# SCH_LinBridge_3_0_2026-08-19_sanitized.net
KiCad netlist of a schematic drawn in EasyEDA
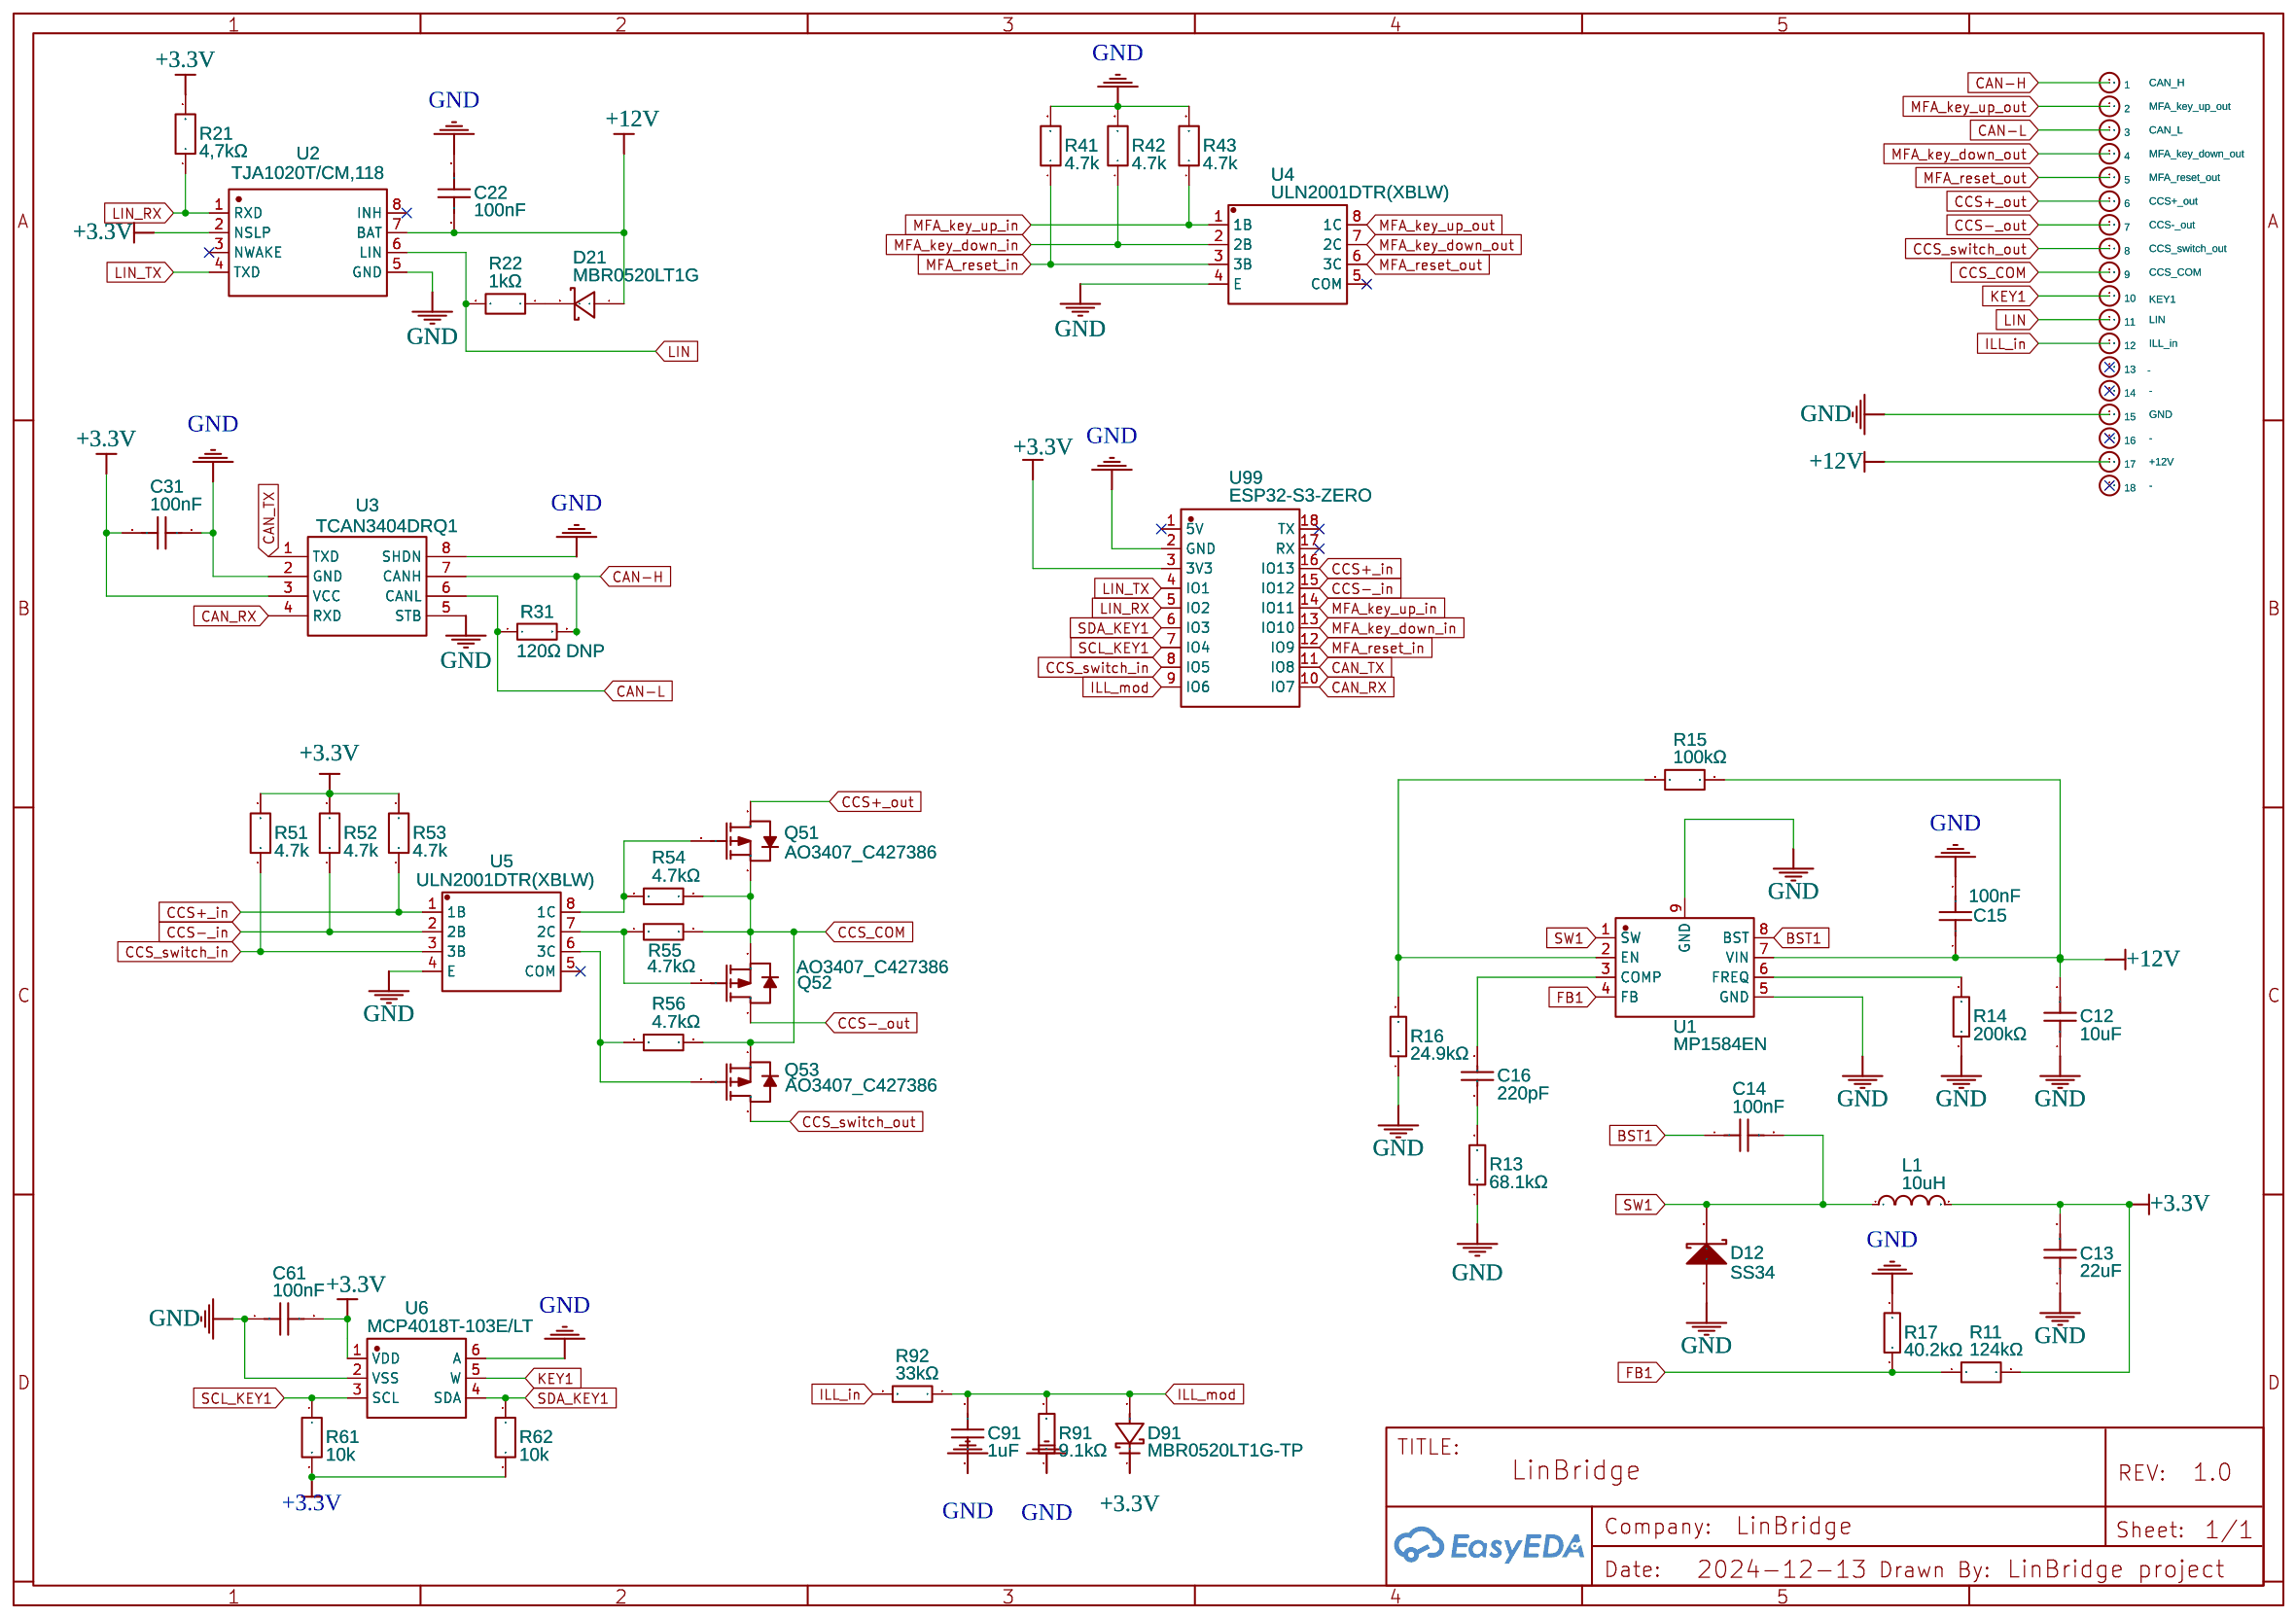
[diagram p0: schematic sheet]

(export (version "E")
  (design (tool "Eeschema 10.0.6"))
  (components
    (comp (ref "1") (value "CAN_H") (libsource (lib "") (part "Through_Hole_1mm")))
    (comp (ref "2") (value "MFA_key_up_out") (libsource (lib "") (part "Through_Hole_1mm")))
    (comp (ref "3") (value "CAN_L") (libsource (lib "") (part "Through_Hole_1mm")))
    (comp (ref "4") (value "MFA_key_down_out") (libsource (lib "") (part "Through_Hole_1mm")))
    (comp (ref "5") (value "MFA_reset_out") (libsource (lib "") (part "Through_Hole_1mm")))
    (comp (ref "6") (value "CCS+_out") (libsource (lib "") (part "Through_Hole_1mm")))
    (comp (ref "7") (value "CCS-_out") (libsource (lib "") (part "Through_Hole_1mm")))
    (comp (ref "8") (value "CCS_switch_out") (libsource (lib "") (part "Through_Hole_1mm")))
    (comp (ref "9") (value "CCS_COM") (libsource (lib "") (part "Through_Hole_1mm")))
    (comp (ref "10") (value "KEY1") (libsource (lib "") (part "Through_Hole_1mm")))
    (comp (ref "11") (value "LIN") (libsource (lib "") (part "Through_Hole_1mm")))
    (comp (ref "12") (value "ILL_in") (libsource (lib "") (part "Through_Hole_1mm")))
    (comp (ref "13") (value "-") (libsource (lib "") (part "Through_Hole_1mm")))
    (comp (ref "14") (value "-") (libsource (lib "") (part "Through_Hole_1mm")))
    (comp (ref "15") (value "GND") (libsource (lib "") (part "Through_Hole_1mm")))
    (comp (ref "16") (value "-") (libsource (lib "") (part "Through_Hole_1mm")))
    (comp (ref "17") (value "+12V") (libsource (lib "") (part "Through_Hole_1mm")))
    (comp (ref "18") (value "-") (libsource (lib "") (part "Through_Hole_1mm")))
    (comp (ref "C12") (value "10uF") (libsource (lib "") (part "TCC1206X5R106K500HT")))
    (comp (ref "C13") (value "22uF") (libsource (lib "") (part "TCC1206X7R226M100HT")))
    (comp (ref "C14") (value "100nF") (libsource (lib "") (part "TCC0603X7R104K250CT")))
    (comp (ref "C15")
      (value "100nF")
      (fields
        (field (name "Manufacturer Part") "C0805C104K5RAC7411")
        (field (name "Manufacturer") "KEMET(基美)")
      )
      (libsource (lib "") (part "C0805C104K5RAC7411"))
    )
    (comp (ref "C16") (value "220pF") (libsource (lib "") (part "CC0603JRNPO9BN221")))
    (comp (ref "C22")
      (value "100nF")
      (fields
        (field (name "Manufacturer Part") "C0805C104K5RAC7411")
        (field (name "Manufacturer") "KEMET(基美)")
      )
      (libsource (lib "") (part "C0805C104K5RAC7411"))
    )
    (comp (ref "C31")
      (value "100nF")
      (fields (field (name "Manufacturer Part") "C0805X104K050T") (field (name "Manufacturer") "IHHEC(禾伸堂)"))
      (libsource (lib "") (part "C0805-100NF"))
    )
    (comp (ref "C61")
      (value "100nF")
      (fields
        (field (name "Manufacturer Part") "CC0805KRX7R7BB104")
        (field (name "Manufacturer") "YAGEO(国巨)")
      )
      (libsource (lib "") (part "CC0805KRX7R7BB104"))
    )
    (comp (ref "C91")
      (value "1uF")
      (fields (field (name "Manufacturer Part") "C0805C105K5RACTU") (field (name "Manufacturer") "KEMET(基美)"))
      (libsource (lib "") (part "C0805C105K5RACTU"))
    )
    (comp (ref "D12")
      (value "SS34")
      (fields (field (name "Manufacturer") "ON"))
      (libsource (lib "") (part "Unknown_842_-178"))
    )
    (comp (ref "D21") (value "MBR0520LT1G") (libsource (lib "") (part "MBR0520LT1G")))
    (comp (ref "D91")
      (value "MBR0520LT1G-TP")
      (fields (field (name "Manufacturer") "TECH PUBLIC(台舟)"))
      (libsource (lib "") (part "MBR0520LT1G-TP"))
    )
    (comp (ref "L1")
      (value "10uH")
      (fields (field (name "Manufacturer Part") "SMNR4020-10UH") (field (name "Manufacturer") "SXN(顺翔诺)"))
      (libsource (lib "") (part "SMNR4020-10UH"))
    )
    (comp (ref "Q51")
      (value "AO3407_C427386")
      (fields (field (name "Manufacturer Part") "MDD3407") (field (name "Manufacturer") "MDD(辰达半导体)"))
      (libsource (lib "") (part "AO3407_C427386_1"))
    )
    (comp (ref "Q52")
      (value "AO3407_C427386")
      (fields (field (name "Manufacturer Part") "MDD3407") (field (name "Manufacturer") "MDD(辰达半导体)"))
      (libsource (lib "") (part "AO3407_C427386"))
    )
    (comp (ref "Q53")
      (value "AO3407_C427386")
      (fields (field (name "Manufacturer Part") "MDD3407") (field (name "Manufacturer") "MDD(辰达半导体)"))
      (libsource (lib "") (part "AO3407_C427386"))
    )
    (comp (ref "R11") (value "124kΩ") (libsource (lib "") (part "TD03G1243BT")))
    (comp (ref "R13") (value "68.1kΩ") (libsource (lib "") (part "0402WGF6812TCE")))
    (comp (ref "R14") (value "200kΩ") (libsource (lib "") (part "CR1206F42003G")))
    (comp (ref "R15") (value "100kΩ") (libsource (lib "") (part "1210W2F1003T5E")))
    (comp (ref "R16") (value "24.9kΩ") (libsource (lib "") (part "0402WGF2492TCE")))
    (comp (ref "R17") (value "40.2kΩ") (libsource (lib "") (part "RTT034022FTP")))
    (comp (ref "R21")
      (value "4,7kΩ")
      (fields (field (name "Manufacturer Part") "APC0805B1K00N") (field (name "Manufacturer") "Ohmite"))
      (libsource (lib "") (part "APC0805B1K00N"))
    )
    (comp (ref "R22")
      (value "1kΩ")
      (fields (field (name "Manufacturer Part") "APC0805B1K00N") (field (name "Manufacturer") "Ohmite"))
      (libsource (lib "") (part "APC0805B1K00N_1"))
    )
    (comp (ref "R31")
      (value "120Ω DNP")
      (fields (field (name "Manufacturer Part") "TC052B1200T5E") (field (name "Manufacturer") "UniOhm"))
      (libsource (lib "") (part "120Ω 0,1%"))
    )
    (comp (ref "R41")
      (value "4.7k")
      (fields (field (name "Manufacturer Part") "RC0805FR-074K7L") (field (name "Manufacturer") "YAGEO(国巨)"))
      (libsource (lib "") (part "R_0603_EU"))
    )
    (comp (ref "R42")
      (value "4.7k")
      (fields (field (name "Manufacturer Part") "RC0805FR-074K7L") (field (name "Manufacturer") "YAGEO(国巨)"))
      (libsource (lib "") (part "R_0603_EU"))
    )
    (comp (ref "R43")
      (value "4.7k")
      (fields (field (name "Manufacturer Part") "RC0805FR-074K7L") (field (name "Manufacturer") "YAGEO(国巨)"))
      (libsource (lib "") (part "R_0603_EU"))
    )
    (comp (ref "R51")
      (value "4.7k")
      (fields (field (name "Manufacturer Part") "RC0805FR-074K7L") (field (name "Manufacturer") "YAGEO(国巨)"))
      (libsource (lib "") (part "R_0603_EU"))
    )
    (comp (ref "R52")
      (value "4.7k")
      (fields (field (name "Manufacturer Part") "RC0805FR-074K7L") (field (name "Manufacturer") "YAGEO(国巨)"))
      (libsource (lib "") (part "R_0603_EU"))
    )
    (comp (ref "R53")
      (value "4.7k")
      (fields (field (name "Manufacturer Part") "RC0805FR-074K7L") (field (name "Manufacturer") "YAGEO(国巨)"))
      (libsource (lib "") (part "R_0603_EU"))
    )
    (comp (ref "R54")
      (value "4.7kΩ")
      (fields (field (name "Manufacturer Part") "RMC08054.7K1%N") (field (name "Manufacturer") "Tyohm(幸亚电阻)"))
      (libsource (lib "") (part "RMC08054.7K1%N"))
    )
    (comp (ref "R55")
      (value "4.7kΩ")
      (fields (field (name "Manufacturer Part") "RMC08054.7K1%N") (field (name "Manufacturer") "Tyohm(幸亚电阻)"))
      (libsource (lib "") (part "RMC08054.7K1%N"))
    )
    (comp (ref "R56")
      (value "4.7kΩ")
      (fields (field (name "Manufacturer Part") "RMC08054.7K1%N") (field (name "Manufacturer") "Tyohm(幸亚电阻)"))
      (libsource (lib "") (part "RMC08054.7K1%N"))
    )
    (comp (ref "R61")
      (value "10k")
      (fields (field (name "Manufacturer Part") "SCR0805F10K") (field (name "Manufacturer") "VO(翔胜)"))
      (libsource (lib "") (part "R_0603_EU_1"))
    )
    (comp (ref "R62")
      (value "10k")
      (fields (field (name "Manufacturer Part") "SCR0805F10K") (field (name "Manufacturer") "VO(翔胜)"))
      (libsource (lib "") (part "R_0603_EU_1"))
    )
    (comp (ref "R91")
      (value "9.1kΩ")
      (fields (field (name "Manufacturer Part") "RMC08059.1K1%N") (field (name "Manufacturer") "Tyohm(幸亚电阻)"))
      (libsource (lib "") (part "RMC08059.1K1%N"))
    )
    (comp (ref "R92")
      (value "33kΩ")
      (fields (field (name "Manufacturer Part") "AECR0805F27K0K9") (field (name "Manufacturer") "RESI(开步睿思)"))
      (libsource (lib "") (part "AECR0805F27K0K9"))
    )
    (comp (ref "U1") (value "MP1584EN") (libsource (lib "") (part "MP1584EN")))
    (comp (ref "U2")
      (value "TJA1020T/CM,118")
      (fields (field (name "Manufacturer") "NXP(恩智浦)"))
      (libsource (lib "") (part "TJA1020T/CM,118"))
    )
    (comp (ref "U3")
      (value "TCAN3404DRQ1")
      (fields (field (name "Manufacturer Part") "TJA1050T/CM,118") (field (name "Manufacturer") "NXP"))
      (libsource (lib "") (part "TJA1050T/CM,118"))
    )
    (comp (ref "U4")
      (value "ULN2001DTR(XBLW)")
      (fields (field (name "Manufacturer") "XBLW(芯伯乐)"))
      (libsource (lib "") (part "ULN2001DTR(XBLW)"))
    )
    (comp (ref "U5")
      (value "ULN2001DTR(XBLW)")
      (fields (field (name "Manufacturer") "XBLW(芯伯乐)"))
      (libsource (lib "") (part "ULN2001DTR(XBLW)"))
    )
    (comp (ref "U6")
      (value "MCP4018T-103E/LT")
      (fields
        (field (name "Manufacturer Part") "MCP4018T-104E/LT")
        (field (name "Manufacturer") "MICROCHIP(美国微芯)")
      )
      (libsource (lib "") (part "MCP4018T-104E/LT"))
    )
    (comp (ref "U99")
      (value "ESP32-S3-ZERO")
      (fields (field (name "Manufacturer Part") "ESP32-S3-Zero"))
      (libsource (lib "") (part "ESP32-S3-ZERO"))
    )
  )
  (nets
    (net (code "1") (name "+3.3V") (class "Default")
      (node (ref "C13") (pin "2") (pinfunction "2_2") (pintype "unspecified"))
      (node (ref "C31") (pin "2") (pinfunction "2_2") (pintype "unspecified"))
      (node (ref "C61") (pin "2") (pinfunction "2_2") (pintype "unspecified"))
      (node (ref "D91") (pin "1") (pinfunction "K_1") (pintype "unspecified"))
      (node (ref "L1") (pin "2") (pinfunction "2_2") (pintype "unspecified"))
      (node (ref "R11") (pin "2") (pinfunction "2_2") (pintype "unspecified"))
      (node (ref "R21") (pin "2") (pinfunction "2_2") (pintype "unspecified"))
      (node (ref "R51") (pin "2") (pinfunction "2_2") (pintype "unspecified"))
      (node (ref "R52") (pin "2") (pinfunction "2_2") (pintype "unspecified"))
      (node (ref "R53") (pin "2") (pinfunction "2_2") (pintype "unspecified"))
      (node (ref "R61") (pin "2") (pinfunction "2_2") (pintype "unspecified"))
      (node (ref "R62") (pin "2") (pinfunction "2_2") (pintype "unspecified"))
      (node (ref "U2") (pin "2") (pinfunction "NSLP_2") (pintype "unspecified"))
      (node (ref "U3") (pin "3") (pinfunction "VCC_3") (pintype "unspecified"))
      (node (ref "U6") (pin "1") (pinfunction "VDD_1") (pintype "unspecified"))
      (node (ref "U99") (pin "3") (pinfunction "3V3_3") (pintype "unspecified"))
    )
    (net (code "2") (name "+12V") (class "Default")
      (node (ref "17") (pin "1") (pinfunction "1_1") (pintype "unspecified"))
      (node (ref "C12") (pin "2") (pinfunction "2_2") (pintype "unspecified"))
      (node (ref "C15") (pin "1") (pinfunction "1_1") (pintype "unspecified"))
      (node (ref "C22") (pin "1") (pinfunction "1_1") (pintype "unspecified"))
      (node (ref "D21") (pin "1") (pinfunction "A_1") (pintype "unspecified"))
      (node (ref "R15") (pin "2") (pinfunction "2_2") (pintype "unspecified"))
      (node (ref "U1") (pin "7") (pinfunction "VIN_7") (pintype "unspecified"))
      (node (ref "U2") (pin "7") (pinfunction "BAT_7") (pintype "unspecified"))
    )
    (net (code "3") (name "BST1") (class "Default")
      (node (ref "C14") (pin "1") (pinfunction "1_1") (pintype "unspecified"))
      (node (ref "U1") (pin "8") (pinfunction "BST_8") (pintype "unspecified"))
    )
    (net (code "4") (name "CAN-H") (class "Default")
      (node (ref "1") (pin "1") (pinfunction "1_1") (pintype "unspecified"))
      (node (ref "R31") (pin "2") (pinfunction "2_2") (pintype "input"))
      (node (ref "U3") (pin "7") (pinfunction "CANH_7") (pintype "unspecified"))
    )
    (net (code "5") (name "CAN-L") (class "Default")
      (node (ref "3") (pin "1") (pinfunction "1_1") (pintype "unspecified"))
      (node (ref "R31") (pin "1") (pinfunction "1_1") (pintype "input"))
      (node (ref "U3") (pin "6") (pinfunction "CANL_6") (pintype "unspecified"))
    )
    (net (code "6") (name "CAN_RX") (class "Default")
      (node (ref "U3") (pin "4") (pinfunction "RXD_4") (pintype "unspecified"))
      (node (ref "U99") (pin "10") (pinfunction "IO7_10") (pintype "unspecified"))
    )
    (net (code "7") (name "CAN_TX") (class "Default")
      (node (ref "U3") (pin "1") (pinfunction "TXD_1") (pintype "unspecified"))
      (node (ref "U99") (pin "11") (pinfunction "IO8_11") (pintype "unspecified"))
    )
    (net (code "8") (name "CCS+_in") (class "Default")
      (node (ref "R53") (pin "1") (pinfunction "1_1") (pintype "unspecified"))
      (node (ref "U5") (pin "1") (pinfunction "1B_1") (pintype "unspecified"))
      (node (ref "U99") (pin "16") (pinfunction "IO13_16") (pintype "unspecified"))
    )
    (net (code "9") (name "CCS+_out") (class "Default")
      (node (ref "6") (pin "1") (pinfunction "1_1") (pintype "unspecified"))
      (node (ref "Q51") (pin "3") (pinfunction "D_3") (pintype "unspecified"))
    )
    (net (code "10") (name "CCS-_in") (class "Default")
      (node (ref "R52") (pin "1") (pinfunction "1_1") (pintype "unspecified"))
      (node (ref "U5") (pin "2") (pinfunction "2B_2") (pintype "unspecified"))
      (node (ref "U99") (pin "15") (pinfunction "IO12_15") (pintype "unspecified"))
    )
    (net (code "11") (name "CCS-_out") (class "Default")
      (node (ref "7") (pin "1") (pinfunction "1_1") (pintype "unspecified"))
      (node (ref "Q52") (pin "3") (pinfunction "D_3") (pintype "unspecified"))
    )
    (net (code "12") (name "CCS_COM") (class "Default")
      (node (ref "9") (pin "1") (pinfunction "1_1") (pintype "unspecified"))
      (node (ref "Q51") (pin "2") (pinfunction "S_2") (pintype "unspecified"))
      (node (ref "Q52") (pin "2") (pinfunction "S_2") (pintype "unspecified"))
      (node (ref "Q53") (pin "2") (pinfunction "S_2") (pintype "unspecified"))
      (node (ref "R54") (pin "2") (pinfunction "2_2") (pintype "unspecified"))
      (node (ref "R55") (pin "2") (pinfunction "2_2") (pintype "unspecified"))
      (node (ref "R56") (pin "2") (pinfunction "2_2") (pintype "unspecified"))
    )
    (net (code "13") (name "CCS_switch_in") (class "Default")
      (node (ref "R51") (pin "1") (pinfunction "1_1") (pintype "unspecified"))
      (node (ref "U5") (pin "3") (pinfunction "3B_3") (pintype "unspecified"))
      (node (ref "U99") (pin "8") (pinfunction "IO5_8") (pintype "unspecified"))
    )
    (net (code "14") (name "CCS_switch_out") (class "Default")
      (node (ref "8") (pin "1") (pinfunction "1_1") (pintype "unspecified"))
      (node (ref "Q53") (pin "3") (pinfunction "D_3") (pintype "unspecified"))
    )
    (net (code "15") (name "FB1") (class "Default")
      (node (ref "R11") (pin "1") (pinfunction "1_1") (pintype "unspecified"))
      (node (ref "R17") (pin "1") (pinfunction "1_1") (pintype "input"))
      (node (ref "U1") (pin "4") (pinfunction "FB_4") (pintype "unspecified"))
    )
    (net (code "16") (name "GND") (class "Default")
      (node (ref "15") (pin "1") (pinfunction "1_1") (pintype "unspecified"))
      (node (ref "C12") (pin "1") (pinfunction "1_1") (pintype "unspecified"))
      (node (ref "C13") (pin "1") (pinfunction "1_1") (pintype "unspecified"))
      (node (ref "C15") (pin "2") (pinfunction "2_2") (pintype "unspecified"))
      (node (ref "C22") (pin "2") (pinfunction "2_2") (pintype "unspecified"))
      (node (ref "C31") (pin "1") (pinfunction "1_1") (pintype "unspecified"))
      (node (ref "C61") (pin "1") (pinfunction "1_1") (pintype "unspecified"))
      (node (ref "C91") (pin "2") (pinfunction "2_2") (pintype "unspecified"))
      (node (ref "D12") (pin "1") (pinfunction "A_1") (pintype "input"))
      (node (ref "R13") (pin "1") (pinfunction "1_1") (pintype "input"))
      (node (ref "R14") (pin "1") (pinfunction "1_1") (pintype "input"))
      (node (ref "R16") (pin "1") (pinfunction "1_1") (pintype "input"))
      (node (ref "R17") (pin "2") (pinfunction "2_2") (pintype "input"))
      (node (ref "R41") (pin "2") (pinfunction "2_2") (pintype "unspecified"))
      (node (ref "R42") (pin "2") (pinfunction "2_2") (pintype "unspecified"))
      (node (ref "R43") (pin "2") (pinfunction "2_2") (pintype "unspecified"))
      (node (ref "R91") (pin "1") (pinfunction "1_1") (pintype "unspecified"))
      (node (ref "U1") (pin "5") (pinfunction "GND_5") (pintype "unspecified"))
      (node (ref "U1") (pin "9") (pinfunction "GND_9") (pintype "unspecified"))
      (node (ref "U2") (pin "5") (pinfunction "GND_5") (pintype "unspecified"))
      (node (ref "U3") (pin "2") (pinfunction "GND_2") (pintype "unspecified"))
      (node (ref "U3") (pin "5") (pinfunction "STB_5") (pintype "unspecified"))
      (node (ref "U3") (pin "8") (pinfunction "SHDN_8") (pintype "unspecified"))
      (node (ref "U4") (pin "4") (pinfunction "E_4") (pintype "unspecified"))
      (node (ref "U5") (pin "4") (pinfunction "E_4") (pintype "unspecified"))
      (node (ref "U6") (pin "2") (pinfunction "VSS_2") (pintype "unspecified"))
      (node (ref "U6") (pin "6") (pinfunction "A_6") (pintype "unspecified"))
      (node (ref "U99") (pin "2") (pinfunction "GND_2") (pintype "unspecified"))
    )
    (net (code "17") (name "ILL_in") (class "Default")
      (node (ref "12") (pin "1") (pinfunction "1_1") (pintype "unspecified"))
      (node (ref "R92") (pin "2") (pinfunction "2_2") (pintype "unspecified"))
    )
    (net (code "18") (name "ILL_mod") (class "Default")
      (node (ref "C91") (pin "1") (pinfunction "1_1") (pintype "unspecified"))
      (node (ref "D91") (pin "2") (pinfunction "A_2") (pintype "unspecified"))
      (node (ref "R91") (pin "2") (pinfunction "2_2") (pintype "unspecified"))
      (node (ref "R92") (pin "1") (pinfunction "1_1") (pintype "unspecified"))
      (node (ref "U99") (pin "9") (pinfunction "IO6_9") (pintype "unspecified"))
    )
    (net (code "19") (name "KEY1") (class "Default")
      (node (ref "10") (pin "1") (pinfunction "1_1") (pintype "unspecified"))
      (node (ref "U6") (pin "5") (pinfunction "W_5") (pintype "unspecified"))
    )
    (net (code "20") (name "LIN") (class "Default")
      (node (ref "11") (pin "1") (pinfunction "1_1") (pintype "unspecified"))
      (node (ref "R22") (pin "2") (pinfunction "2_2") (pintype "unspecified"))
      (node (ref "U2") (pin "6") (pinfunction "LIN_6") (pintype "unspecified"))
    )
    (net (code "21") (name "LIN_RX") (class "Default")
      (node (ref "R21") (pin "1") (pinfunction "1_1") (pintype "unspecified"))
      (node (ref "U2") (pin "1") (pinfunction "RXD_1") (pintype "unspecified"))
      (node (ref "U99") (pin "5") (pinfunction "IO2_5") (pintype "unspecified"))
    )
    (net (code "22") (name "LIN_TX") (class "Default")
      (node (ref "U2") (pin "4") (pinfunction "TXD_4") (pintype "unspecified"))
      (node (ref "U99") (pin "4") (pinfunction "IO1_4") (pintype "unspecified"))
    )
    (net (code "23") (name "MFA_key_down_in") (class "Default")
      (node (ref "R42") (pin "1") (pinfunction "1_1") (pintype "unspecified"))
      (node (ref "U4") (pin "2") (pinfunction "2B_2") (pintype "unspecified"))
      (node (ref "U99") (pin "13") (pinfunction "IO10_13") (pintype "unspecified"))
    )
    (net (code "24") (name "MFA_key_down_out") (class "Default")
      (node (ref "4") (pin "1") (pinfunction "1_1") (pintype "unspecified"))
      (node (ref "U4") (pin "7") (pinfunction "2C_7") (pintype "unspecified"))
    )
    (net (code "25") (name "MFA_key_up_in") (class "Default")
      (node (ref "R43") (pin "1") (pinfunction "1_1") (pintype "unspecified"))
      (node (ref "U4") (pin "1") (pinfunction "1B_1") (pintype "unspecified"))
      (node (ref "U99") (pin "14") (pinfunction "IO11_14") (pintype "unspecified"))
    )
    (net (code "26") (name "MFA_key_up_out") (class "Default")
      (node (ref "2") (pin "1") (pinfunction "1_1") (pintype "unspecified"))
      (node (ref "U4") (pin "8") (pinfunction "1C_8") (pintype "unspecified"))
    )
    (net (code "27") (name "MFA_reset_in") (class "Default")
      (node (ref "R41") (pin "1") (pinfunction "1_1") (pintype "unspecified"))
      (node (ref "U4") (pin "3") (pinfunction "3B_3") (pintype "unspecified"))
      (node (ref "U99") (pin "12") (pinfunction "IO9_12") (pintype "unspecified"))
    )
    (net (code "28") (name "MFA_reset_out") (class "Default")
      (node (ref "5") (pin "1") (pinfunction "1_1") (pintype "unspecified"))
      (node (ref "U4") (pin "6") (pinfunction "3C_6") (pintype "unspecified"))
    )
    (net (code "29") (name "Net-(C16-Pad1)") (class "Default")
      (node (ref "C16") (pin "1") (pinfunction "1_1") (pintype "input"))
      (node (ref "R13") (pin "2") (pinfunction "2_2") (pintype "input"))
    )
    (net (code "30") (name "Net-(D21-K)") (class "Default")
      (node (ref "D21") (pin "2") (pinfunction "K_2") (pintype "unspecified"))
      (node (ref "R22") (pin "1") (pinfunction "1_1") (pintype "unspecified"))
    )
    (net (code "31") (name "Net-(Q51-G)") (class "Default")
      (node (ref "Q51") (pin "1") (pinfunction "G_1") (pintype "unspecified"))
      (node (ref "R54") (pin "1") (pinfunction "1_1") (pintype "unspecified"))
      (node (ref "U5") (pin "8") (pinfunction "1C_8") (pintype "unspecified"))
    )
    (net (code "32") (name "Net-(Q52-G)") (class "Default")
      (node (ref "Q52") (pin "1") (pinfunction "G_1") (pintype "unspecified"))
      (node (ref "R55") (pin "1") (pinfunction "1_1") (pintype "unspecified"))
      (node (ref "U5") (pin "7") (pinfunction "2C_7") (pintype "unspecified"))
    )
    (net (code "33") (name "Net-(Q53-G)") (class "Default")
      (node (ref "Q53") (pin "1") (pinfunction "G_1") (pintype "unspecified"))
      (node (ref "R56") (pin "1") (pinfunction "1_1") (pintype "unspecified"))
      (node (ref "U5") (pin "6") (pinfunction "3C_6") (pintype "unspecified"))
    )
    (net (code "34") (name "Net-(U1-COMP)") (class "Default")
      (node (ref "C16") (pin "2") (pinfunction "2_2") (pintype "input"))
      (node (ref "U1") (pin "3") (pinfunction "COMP_3") (pintype "unspecified"))
    )
    (net (code "35") (name "Net-(U1-EN)") (class "Default")
      (node (ref "R15") (pin "1") (pinfunction "1_1") (pintype "unspecified"))
      (node (ref "R16") (pin "2") (pinfunction "2_2") (pintype "input"))
      (node (ref "U1") (pin "2") (pinfunction "EN_2") (pintype "unspecified"))
    )
    (net (code "36") (name "Net-(U1-FREQ)") (class "Default")
      (node (ref "R14") (pin "2") (pinfunction "2_2") (pintype "input"))
      (node (ref "U1") (pin "6") (pinfunction "FREQ_6") (pintype "unspecified"))
    )
    (net (code "37") (name "SCL_KEY1") (class "Default")
      (node (ref "R61") (pin "1") (pinfunction "1_1") (pintype "unspecified"))
      (node (ref "U6") (pin "3") (pinfunction "SCL_3") (pintype "unspecified"))
      (node (ref "U99") (pin "7") (pinfunction "IO4_7") (pintype "unspecified"))
    )
    (net (code "38") (name "SDA_KEY1") (class "Default")
      (node (ref "R62") (pin "1") (pinfunction "1_1") (pintype "unspecified"))
      (node (ref "U6") (pin "4") (pinfunction "SDA_4") (pintype "unspecified"))
      (node (ref "U99") (pin "6") (pinfunction "IO3_6") (pintype "unspecified"))
    )
    (net (code "39") (name "SW1") (class "Default")
      (node (ref "C14") (pin "2") (pinfunction "2_2") (pintype "unspecified"))
      (node (ref "D12") (pin "2") (pinfunction "K_2") (pintype "input"))
      (node (ref "L1") (pin "1") (pinfunction "1_1") (pintype "unspecified"))
      (node (ref "U1") (pin "1") (pinfunction "SW_1") (pintype "unspecified"))
    )
    (net (code "40") (name "unconnected-(13-Pad1)") (class "Default")
      (node (ref "13") (pin "1") (pinfunction "1_1") (pintype "unspecified+no_connect"))
    )
    (net (code "41") (name "unconnected-(14-Pad1)") (class "Default")
      (node (ref "14") (pin "1") (pinfunction "1_1") (pintype "unspecified+no_connect"))
    )
    (net (code "42") (name "unconnected-(16-Pad1)") (class "Default")
      (node (ref "16") (pin "1") (pinfunction "1_1") (pintype "unspecified+no_connect"))
    )
    (net (code "43") (name "unconnected-(18-Pad1)") (class "Default")
      (node (ref "18") (pin "1") (pinfunction "1_1") (pintype "unspecified+no_connect"))
    )
    (net (code "44") (name "unconnected-(U2-INH-Pad8)") (class "Default")
      (node (ref "U2") (pin "8") (pinfunction "INH_8") (pintype "unspecified+no_connect"))
    )
    (net (code "45") (name "unconnected-(U2-NWAKE-Pad3)") (class "Default")
      (node (ref "U2") (pin "3") (pinfunction "NWAKE_3") (pintype "unspecified+no_connect"))
    )
    (net (code "46") (name "unconnected-(U4-COM-Pad5)") (class "Default")
      (node (ref "U4") (pin "5") (pinfunction "COM_5") (pintype "unspecified+no_connect"))
    )
    (net (code "47") (name "unconnected-(U5-COM-Pad5)") (class "Default")
      (node (ref "U5") (pin "5") (pinfunction "COM_5") (pintype "unspecified+no_connect"))
    )
    (net (code "48") (name "unconnected-(U99-5V-Pad1)") (class "Default")
      (node (ref "U99") (pin "1") (pinfunction "5V_1") (pintype "unspecified+no_connect"))
    )
    (net (code "49") (name "unconnected-(U99-RX-Pad17)") (class "Default")
      (node (ref "U99") (pin "17") (pinfunction "RX_17") (pintype "unspecified+no_connect"))
    )
    (net (code "50") (name "unconnected-(U99-TX-Pad18)") (class "Default")
      (node (ref "U99") (pin "18") (pinfunction "TX_18") (pintype "unspecified+no_connect"))
    )
  )
)
